# ElectronTest.net
KiCad netlist of a schematic drawn in EAGLE
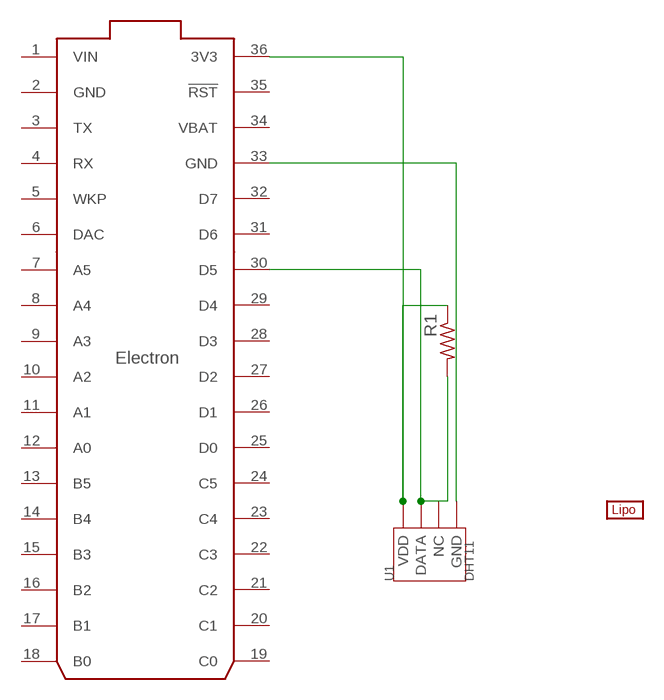
[diagram p0: schematic, sheet 1]

(export (version "E")
  (design (tool "Eeschema 10.0.6"))
  (components
    (comp (ref "BT1")
      (value "LIPO-OUTLINE1100")
      (footprint "eagle-import:LIPO-1000")
      (libsource (lib "eagle-import") (part "LIPO-OUTLINE1100"))
    )
    (comp (ref "R1")
      (value "R-US_R2010W")
      (footprint "eagle-import:R2010W")
      (libsource (lib "eagle-import") (part "R-US_R2010W"))
    )
    (comp (ref "U$1")
      (value "ELECTRON_WITH_HEADERS")
      (footprint "eagle-import:ELECTRON")
      (libsource (lib "eagle-import") (part "ELECTRON_WITH_HEADERS"))
    )
    (comp (ref "U1")
      (value "DHT11")
      (footprint "eagle-import:SNR4-2.54-15.5X12.0X5.5MM")
      (libsource (lib "eagle-import") (part "TEM-HUM-DHT11(4P-15.5X12.0MM)"))
    )
  )
  (nets
    (net (code "1") (name "/GND") (class "Default")
      (node (ref "U$1") (pin "2") (pinfunction "GND_2") (pintype "power_in"))
    )
    (net (code "2") (name "/VBAT") (class "Default")
      (node (ref "U$1") (pin "34") (pinfunction "VBAT_34") (pintype "power_in"))
    )
    (net (code "3") (name "/VIN") (class "Default")
      (node (ref "U$1") (pin "1") (pinfunction "VIN_1") (pintype "power_in"))
    )
    (net (code "4") (name "Net-(U$1-3V3)") (class "Default")
      (node (ref "R1") (pin "1") (pinfunction "1_1") (pintype "passive"))
      (node (ref "U$1") (pin "36") (pinfunction "3V3_36") (pintype "power_in"))
      (node (ref "U1") (pin "1") (pinfunction "VDD_1") (pintype "power_in"))
    )
    (net (code "5") (name "Net-(U$1-D5)") (class "Default")
      (node (ref "R1") (pin "2") (pinfunction "2_2") (pintype "passive"))
      (node (ref "U$1") (pin "30") (pinfunction "D5_30") (pintype "bidirectional"))
      (node (ref "U1") (pin "2") (pinfunction "DATA_2") (pintype "bidirectional"))
    )
    (net (code "6") (name "Net-(U1-GND)") (class "Default")
      (node (ref "U$1") (pin "33") (pinfunction "GND_33") (pintype "power_in"))
      (node (ref "U1") (pin "4") (pinfunction "GND_4") (pintype "power_in"))
    )
    (net (code "7") (name "unconnected-(U$1-A0-Pad12)") (class "Default")
      (node (ref "U$1") (pin "12") (pinfunction "A0_12") (pintype "bidirectional"))
    )
    (net (code "8") (name "unconnected-(U$1-A1-Pad11)") (class "Default")
      (node (ref "U$1") (pin "11") (pinfunction "A1_11") (pintype "bidirectional"))
    )
    (net (code "9") (name "unconnected-(U$1-A2-Pad10)") (class "Default")
      (node (ref "U$1") (pin "10") (pinfunction "A2_10") (pintype "bidirectional"))
    )
    (net (code "10") (name "unconnected-(U$1-A3-Pad9)") (class "Default")
      (node (ref "U$1") (pin "9") (pinfunction "A3_9") (pintype "bidirectional"))
    )
    (net (code "11") (name "unconnected-(U$1-A4-Pad8)") (class "Default")
      (node (ref "U$1") (pin "8") (pinfunction "A4_8") (pintype "bidirectional"))
    )
    (net (code "12") (name "unconnected-(U$1-A5-Pad7)") (class "Default")
      (node (ref "U$1") (pin "7") (pinfunction "A5_7") (pintype "bidirectional"))
    )
    (net (code "13") (name "unconnected-(U$1-B0-Pad18)") (class "Default")
      (node (ref "U$1") (pin "18") (pinfunction "B0_18") (pintype "bidirectional"))
    )
    (net (code "14") (name "unconnected-(U$1-B1-Pad17)") (class "Default")
      (node (ref "U$1") (pin "17") (pinfunction "B1_17") (pintype "bidirectional"))
    )
    (net (code "15") (name "unconnected-(U$1-B2-Pad16)") (class "Default")
      (node (ref "U$1") (pin "16") (pinfunction "B2_16") (pintype "bidirectional"))
    )
    (net (code "16") (name "unconnected-(U$1-B3-Pad15)") (class "Default")
      (node (ref "U$1") (pin "15") (pinfunction "B3_15") (pintype "bidirectional"))
    )
    (net (code "17") (name "unconnected-(U$1-B4-Pad14)") (class "Default")
      (node (ref "U$1") (pin "14") (pinfunction "B4_14") (pintype "bidirectional"))
    )
    (net (code "18") (name "unconnected-(U$1-B5-Pad13)") (class "Default")
      (node (ref "U$1") (pin "13") (pinfunction "B5_13") (pintype "bidirectional"))
    )
    (net (code "19") (name "unconnected-(U$1-C0-Pad19)") (class "Default")
      (node (ref "U$1") (pin "19") (pinfunction "C0_19") (pintype "bidirectional"))
    )
    (net (code "20") (name "unconnected-(U$1-C1-Pad20)") (class "Default")
      (node (ref "U$1") (pin "20") (pinfunction "C1_20") (pintype "bidirectional"))
    )
    (net (code "21") (name "unconnected-(U$1-C2-Pad21)") (class "Default")
      (node (ref "U$1") (pin "21") (pinfunction "C2_21") (pintype "bidirectional"))
    )
    (net (code "22") (name "unconnected-(U$1-C3-Pad22)") (class "Default")
      (node (ref "U$1") (pin "22") (pinfunction "C3_22") (pintype "bidirectional"))
    )
    (net (code "23") (name "unconnected-(U$1-C4-Pad23)") (class "Default")
      (node (ref "U$1") (pin "23") (pinfunction "C4_23") (pintype "bidirectional"))
    )
    (net (code "24") (name "unconnected-(U$1-C5-Pad24)") (class "Default")
      (node (ref "U$1") (pin "24") (pinfunction "C5_24") (pintype "bidirectional"))
    )
    (net (code "25") (name "unconnected-(U$1-D0-Pad25)") (class "Default")
      (node (ref "U$1") (pin "25") (pinfunction "D0_25") (pintype "bidirectional"))
    )
    (net (code "26") (name "unconnected-(U$1-D1-Pad26)") (class "Default")
      (node (ref "U$1") (pin "26") (pinfunction "D1_26") (pintype "bidirectional"))
    )
    (net (code "27") (name "unconnected-(U$1-D2-Pad27)") (class "Default")
      (node (ref "U$1") (pin "27") (pinfunction "D2_27") (pintype "bidirectional"))
    )
    (net (code "28") (name "unconnected-(U$1-D3-Pad28)") (class "Default")
      (node (ref "U$1") (pin "28") (pinfunction "D3_28") (pintype "bidirectional"))
    )
    (net (code "29") (name "unconnected-(U$1-D4-Pad29)") (class "Default")
      (node (ref "U$1") (pin "29") (pinfunction "D4_29") (pintype "bidirectional"))
    )
    (net (code "30") (name "unconnected-(U$1-D6-Pad31)") (class "Default")
      (node (ref "U$1") (pin "31") (pinfunction "D6_31") (pintype "bidirectional"))
    )
    (net (code "31") (name "unconnected-(U$1-D7-Pad32)") (class "Default")
      (node (ref "U$1") (pin "32") (pinfunction "D7_32") (pintype "bidirectional"))
    )
    (net (code "32") (name "unconnected-(U$1-DAC-Pad6)") (class "Default")
      (node (ref "U$1") (pin "6") (pinfunction "DAC_6") (pintype "bidirectional"))
    )
    (net (code "33") (name "unconnected-(U$1-RX-Pad4)") (class "Default")
      (node (ref "U$1") (pin "4") (pinfunction "RX_4") (pintype "bidirectional"))
    )
    (net (code "34") (name "unconnected-(U$1-TX-Pad3)") (class "Default")
      (node (ref "U$1") (pin "3") (pinfunction "TX_3") (pintype "bidirectional"))
    )
    (net (code "35") (name "unconnected-(U$1-WKP-Pad5)") (class "Default")
      (node (ref "U$1") (pin "5") (pinfunction "WKP_5") (pintype "bidirectional"))
    )
    (net (code "36") (name "unconnected-(U$1-~{RST}-Pad35)") (class "Default")
      (node (ref "U$1") (pin "35") (pinfunction "~{RST}_35") (pintype "bidirectional"))
    )
    (net (code "37") (name "unconnected-(U1-NC-Pad3)") (class "Default")
      (node (ref "U1") (pin "3") (pinfunction "NC_3") (pintype "no_connect"))
    )
  )
)
